# stepper_driver.net
KiCad netlist of a schematic drawn in Altium Designer
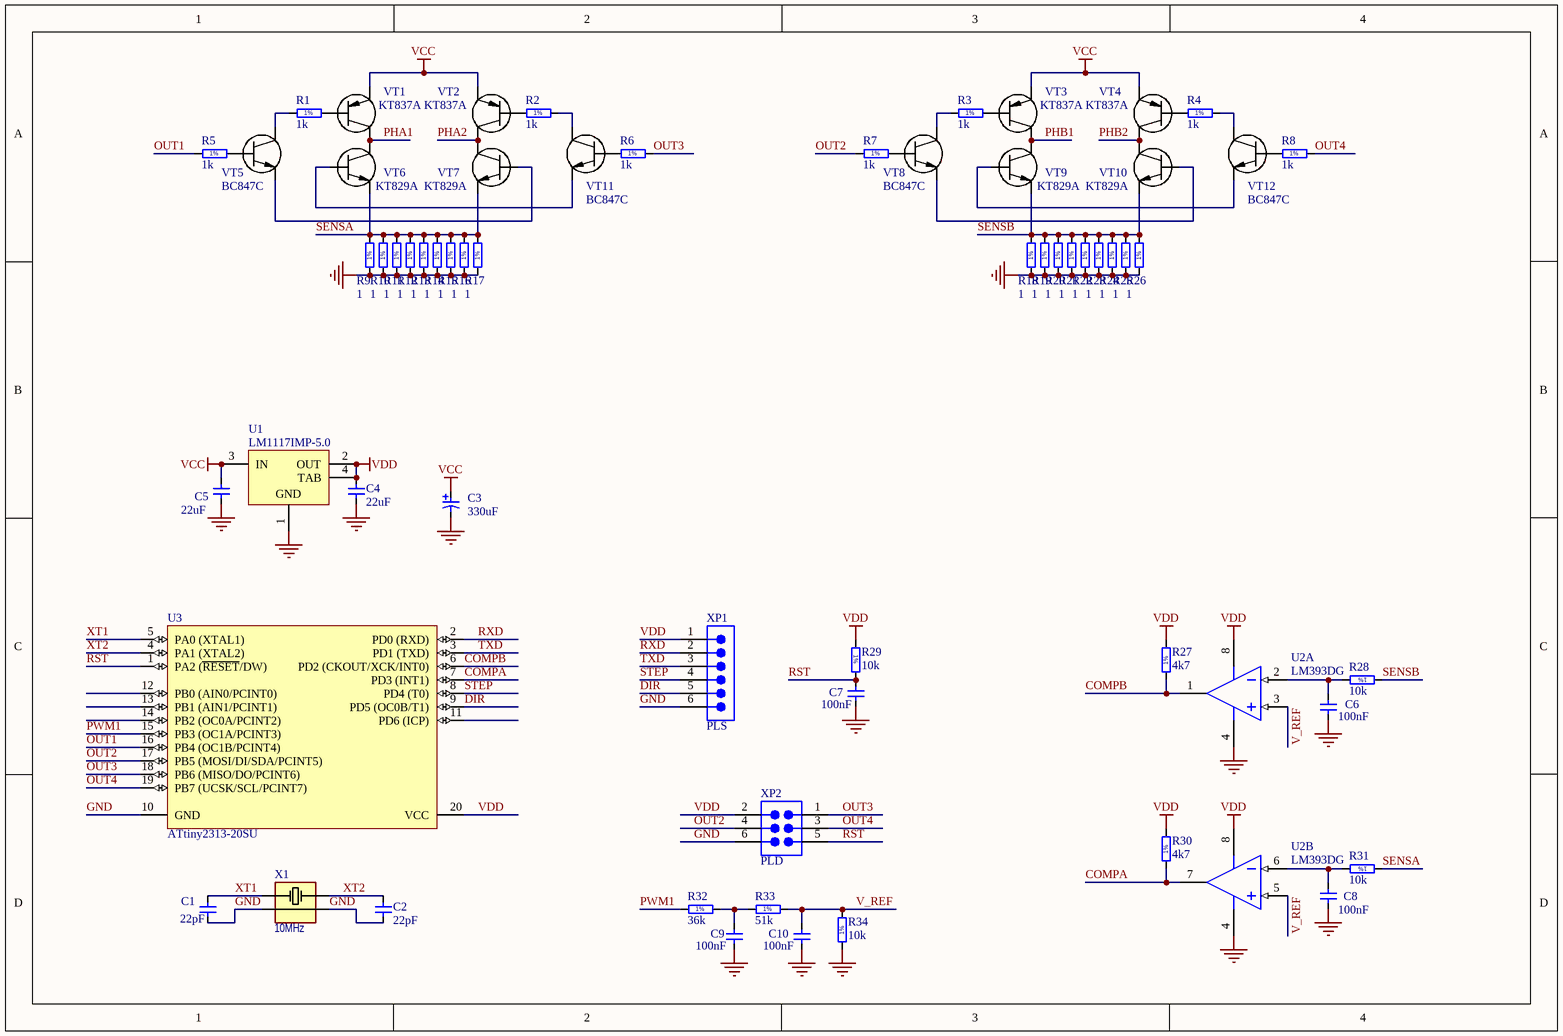
[diagram p0: stepper_driver.SchDoc]

(export (version "E")
  (design (tool "Eeschema 10.0.6"))
  (components
    (comp (ref "C1")
      (value "22pF")
      (footprint "CAP0805R")
      (description "SMD 0805 Capacitor")
      (fields
        (field (name "PART NUMBER") "CC0805_22PF_50V_5%_NP0")
        (field (name "VOLTAGE") "50V")
        (field (name "AUTHOR") "I. Kuznetsov")
      )
      (libsource (lib "Capacitor") (part "CAP_NON_POLAR"))
    )
    (comp (ref "C2")
      (value "22pF")
      (footprint "CAP0805R")
      (description "SMD 0805 Capacitor")
      (fields
        (field (name "PART NUMBER") "CC0805_22PF_50V_5%_NP0")
        (field (name "VOLTAGE") "50V")
        (field (name "AUTHOR") "I. Kuznetsov")
      )
      (libsource (lib "Capacitor") (part "CAP_NON_POLAR"))
    )
    (comp (ref "C3")
      (value "330uF")
      (footprint "TAN_D")
      (fields (field (name "PART NUMBER") "T495D337M010AHE100") (field (name "VOLTAGE") "10V"))
      (libsource (lib "Capacitor") (part "CAP_POLAR"))
    )
    (comp (ref "C4")
      (value "22uF")
      (footprint "CAP0805R")
      (description "SMD 0805 Capacitor")
      (fields
        (field (name "PART NUMBER") "CC0805_22UF_16V_10%_X5R")
        (field (name "VOLTAGE") "16V")
        (field (name "AUTHOR") "I. Kuznetsov")
      )
      (libsource (lib "Capacitor") (part "CAP_NON_POLAR"))
    )
    (comp (ref "C5")
      (value "22uF")
      (footprint "CAP0805R")
      (description "SMD 0805 Capacitor")
      (fields
        (field (name "PART NUMBER") "CC0805_22UF_16V_10%_X5R")
        (field (name "VOLTAGE") "16V")
        (field (name "AUTHOR") "I. Kuznetsov")
      )
      (libsource (lib "Capacitor") (part "CAP_NON_POLAR"))
    )
    (comp (ref "C6")
      (value "100nF")
      (footprint "CAP0805R")
      (description "SMD 0805 Capacitor")
      (fields
        (field (name "PART NUMBER") "CC0805_100NF_50V_10%_X7R")
        (field (name "VOLTAGE") "50V")
        (field (name "AUTHOR") "I. Kuznetsov")
      )
      (libsource (lib "Capacitor") (part "CAP_NON_POLAR"))
    )
    (comp (ref "C7")
      (value "100nF")
      (footprint "CAP0805R")
      (description "SMD 0805 Capacitor")
      (fields
        (field (name "PART NUMBER") "CC0805_100NF_50V_10%_X7R")
        (field (name "VOLTAGE") "50V")
        (field (name "AUTHOR") "I. Kuznetsov")
      )
      (libsource (lib "Capacitor") (part "CAP_NON_POLAR"))
    )
    (comp (ref "C8")
      (value "100nF")
      (footprint "CAP0805R")
      (description "SMD 0805 Capacitor")
      (fields
        (field (name "PART NUMBER") "CC0805_100NF_50V_10%_X7R")
        (field (name "VOLTAGE") "50V")
        (field (name "AUTHOR") "I. Kuznetsov")
      )
      (libsource (lib "Capacitor") (part "CAP_NON_POLAR"))
    )
    (comp (ref "C9")
      (value "100nF")
      (footprint "CAP0805R")
      (description "SMD 0805 Capacitor")
      (fields
        (field (name "PART NUMBER") "CC0805_100NF_50V_10%_X7R")
        (field (name "VOLTAGE") "50V")
        (field (name "AUTHOR") "I. Kuznetsov")
      )
      (libsource (lib "Capacitor") (part "CAP_NON_POLAR"))
    )
    (comp (ref "C10")
      (value "100nF")
      (footprint "CAP0805R")
      (description "SMD 0805 Capacitor")
      (fields
        (field (name "PART NUMBER") "CC0805_100NF_50V_10%_X7R")
        (field (name "VOLTAGE") "50V")
        (field (name "AUTHOR") "I. Kuznetsov")
      )
      (libsource (lib "Capacitor") (part "CAP_NON_POLAR"))
    )
    (comp (ref "R1")
      (value "1k")
      (footprint "RES0805R")
      (fields
        (field (name "PART NUMBER") "R0805_1K_1%_0.125W_100PPM")
        (field (name "POWER") "0.125W")
        (field (name "TOLERANCE") "±1%")
        (field (name "AUTHOR") "CERN DEM JLC")
      )
      (libsource (lib "Resistor") (part "Resistor - 1%"))
    )
    (comp (ref "R2")
      (value "1k")
      (footprint "RES0805R")
      (fields
        (field (name "PART NUMBER") "R0805_1K_1%_0.125W_100PPM")
        (field (name "POWER") "0.125W")
        (field (name "TOLERANCE") "±1%")
        (field (name "AUTHOR") "CERN DEM JLC")
      )
      (libsource (lib "Resistor") (part "Resistor - 1%"))
    )
    (comp (ref "R3")
      (value "1k")
      (footprint "RES0805R")
      (fields
        (field (name "PART NUMBER") "R0805_1K_1%_0.125W_100PPM")
        (field (name "POWER") "0.125W")
        (field (name "TOLERANCE") "±1%")
        (field (name "AUTHOR") "CERN DEM JLC")
      )
      (libsource (lib "Resistor") (part "Resistor - 1%"))
    )
    (comp (ref "R4")
      (value "1k")
      (footprint "RES0805R")
      (fields
        (field (name "PART NUMBER") "R0805_1K_1%_0.125W_100PPM")
        (field (name "POWER") "0.125W")
        (field (name "TOLERANCE") "±1%")
        (field (name "AUTHOR") "CERN DEM JLC")
      )
      (libsource (lib "Resistor") (part "Resistor - 1%"))
    )
    (comp (ref "R5")
      (value "1k")
      (footprint "RES0805R")
      (fields
        (field (name "PART NUMBER") "R0805_1K_1%_0.125W_100PPM")
        (field (name "POWER") "0.125W")
        (field (name "TOLERANCE") "±1%")
        (field (name "AUTHOR") "CERN DEM JLC")
      )
      (libsource (lib "Resistor") (part "Resistor - 1%"))
    )
    (comp (ref "R6")
      (value "1k")
      (footprint "RES0805R")
      (fields
        (field (name "PART NUMBER") "R0805_1K_1%_0.125W_100PPM")
        (field (name "POWER") "0.125W")
        (field (name "TOLERANCE") "±1%")
        (field (name "AUTHOR") "CERN DEM JLC")
      )
      (libsource (lib "Resistor") (part "Resistor - 1%"))
    )
    (comp (ref "R7")
      (value "1k")
      (footprint "RES0805R")
      (fields
        (field (name "PART NUMBER") "R0805_1K_1%_0.125W_100PPM")
        (field (name "POWER") "0.125W")
        (field (name "TOLERANCE") "±1%")
        (field (name "AUTHOR") "CERN DEM JLC")
      )
      (libsource (lib "Resistor") (part "Resistor - 1%"))
    )
    (comp (ref "R8")
      (value "1k")
      (footprint "RES0805R")
      (fields
        (field (name "PART NUMBER") "R0805_1K_1%_0.125W_100PPM")
        (field (name "POWER") "0.125W")
        (field (name "TOLERANCE") "±1%")
        (field (name "AUTHOR") "CERN DEM JLC")
      )
      (libsource (lib "Resistor") (part "Resistor - 1%"))
    )
    (comp (ref "R9")
      (value "1")
      (footprint "RES1206R")
      (fields
        (field (name "PART NUMBER") "R1206_1R_1%_0.25W_200PPM")
        (field (name "POWER") "0.25W")
        (field (name "TOLERANCE") "±1%")
        (field (name "AUTHOR") "CERN DEM JLC")
      )
      (libsource (lib "Resistor") (part "Resistor - 1%"))
    )
    (comp (ref "R10")
      (value "1")
      (footprint "RES1206R")
      (fields
        (field (name "PART NUMBER") "R1206_1R_1%_0.25W_200PPM")
        (field (name "POWER") "0.25W")
        (field (name "TOLERANCE") "±1%")
        (field (name "AUTHOR") "CERN DEM JLC")
      )
      (libsource (lib "Resistor") (part "Resistor - 1%"))
    )
    (comp (ref "R11")
      (value "1")
      (footprint "RES1206R")
      (fields
        (field (name "PART NUMBER") "R1206_1R_1%_0.25W_200PPM")
        (field (name "POWER") "0.25W")
        (field (name "TOLERANCE") "±1%")
        (field (name "AUTHOR") "CERN DEM JLC")
      )
      (libsource (lib "Resistor") (part "Resistor - 1%"))
    )
    (comp (ref "R12")
      (value "1")
      (footprint "RES1206R")
      (fields
        (field (name "PART NUMBER") "R1206_1R_1%_0.25W_200PPM")
        (field (name "POWER") "0.25W")
        (field (name "TOLERANCE") "±1%")
        (field (name "AUTHOR") "CERN DEM JLC")
      )
      (libsource (lib "Resistor") (part "Resistor - 1%"))
    )
    (comp (ref "R13")
      (value "1")
      (footprint "RES1206R")
      (fields
        (field (name "PART NUMBER") "R1206_1R_1%_0.25W_200PPM")
        (field (name "POWER") "0.25W")
        (field (name "TOLERANCE") "±1%")
        (field (name "AUTHOR") "CERN DEM JLC")
      )
      (libsource (lib "Resistor") (part "Resistor - 1%"))
    )
    (comp (ref "R14")
      (value "1")
      (footprint "RES1206R")
      (fields
        (field (name "PART NUMBER") "R1206_1R_1%_0.25W_200PPM")
        (field (name "POWER") "0.25W")
        (field (name "TOLERANCE") "±1%")
        (field (name "AUTHOR") "CERN DEM JLC")
      )
      (libsource (lib "Resistor") (part "Resistor - 1%"))
    )
    (comp (ref "R15")
      (value "1")
      (footprint "RES1206R")
      (fields
        (field (name "PART NUMBER") "R1206_1R_1%_0.25W_200PPM")
        (field (name "POWER") "0.25W")
        (field (name "TOLERANCE") "±1%")
        (field (name "AUTHOR") "CERN DEM JLC")
      )
      (libsource (lib "Resistor") (part "Resistor - 1%"))
    )
    (comp (ref "R16")
      (value "1")
      (footprint "RES1206R")
      (fields
        (field (name "PART NUMBER") "R1206_1R_1%_0.25W_200PPM")
        (field (name "POWER") "0.25W")
        (field (name "TOLERANCE") "±1%")
        (field (name "AUTHOR") "CERN DEM JLC")
      )
      (libsource (lib "Resistor") (part "Resistor - 1%"))
    )
    (comp (ref "R17")
      (value "1")
      (footprint "RES1206R")
      (fields
        (field (name "PART NUMBER") "R1206_1R_1%_0.25W_200PPM")
        (field (name "POWER") "0.25W")
        (field (name "TOLERANCE") "±1%")
        (field (name "AUTHOR") "CERN DEM JLC")
      )
      (libsource (lib "Resistor") (part "Resistor - 1%"))
    )
    (comp (ref "R18")
      (value "1")
      (footprint "RES1206R")
      (fields
        (field (name "PART NUMBER") "R1206_1R_1%_0.25W_200PPM")
        (field (name "POWER") "0.25W")
        (field (name "TOLERANCE") "±1%")
        (field (name "AUTHOR") "CERN DEM JLC")
      )
      (libsource (lib "Resistor") (part "Resistor - 1%"))
    )
    (comp (ref "R19")
      (value "1")
      (footprint "RES1206R")
      (fields
        (field (name "PART NUMBER") "R1206_1R_1%_0.25W_200PPM")
        (field (name "POWER") "0.25W")
        (field (name "TOLERANCE") "±1%")
        (field (name "AUTHOR") "CERN DEM JLC")
      )
      (libsource (lib "Resistor") (part "Resistor - 1%"))
    )
    (comp (ref "R20")
      (value "1")
      (footprint "RES1206R")
      (fields
        (field (name "PART NUMBER") "R1206_1R_1%_0.25W_200PPM")
        (field (name "POWER") "0.25W")
        (field (name "TOLERANCE") "±1%")
        (field (name "AUTHOR") "CERN DEM JLC")
      )
      (libsource (lib "Resistor") (part "Resistor - 1%"))
    )
    (comp (ref "R21")
      (value "1")
      (footprint "RES1206R")
      (fields
        (field (name "PART NUMBER") "R1206_1R_1%_0.25W_200PPM")
        (field (name "POWER") "0.25W")
        (field (name "TOLERANCE") "±1%")
        (field (name "AUTHOR") "CERN DEM JLC")
      )
      (libsource (lib "Resistor") (part "Resistor - 1%"))
    )
    (comp (ref "R22")
      (value "1")
      (footprint "RES1206R")
      (fields
        (field (name "PART NUMBER") "R1206_1R_1%_0.25W_200PPM")
        (field (name "POWER") "0.25W")
        (field (name "TOLERANCE") "±1%")
        (field (name "AUTHOR") "CERN DEM JLC")
      )
      (libsource (lib "Resistor") (part "Resistor - 1%"))
    )
    (comp (ref "R23")
      (value "1")
      (footprint "RES1206R")
      (fields
        (field (name "PART NUMBER") "R1206_1R_1%_0.25W_200PPM")
        (field (name "POWER") "0.25W")
        (field (name "TOLERANCE") "±1%")
        (field (name "AUTHOR") "CERN DEM JLC")
      )
      (libsource (lib "Resistor") (part "Resistor - 1%"))
    )
    (comp (ref "R24")
      (value "1")
      (footprint "RES1206R")
      (fields
        (field (name "PART NUMBER") "R1206_1R_1%_0.25W_200PPM")
        (field (name "POWER") "0.25W")
        (field (name "TOLERANCE") "±1%")
        (field (name "AUTHOR") "CERN DEM JLC")
      )
      (libsource (lib "Resistor") (part "Resistor - 1%"))
    )
    (comp (ref "R25")
      (value "1")
      (footprint "RES1206R")
      (fields
        (field (name "PART NUMBER") "R1206_1R_1%_0.25W_200PPM")
        (field (name "POWER") "0.25W")
        (field (name "TOLERANCE") "±1%")
        (field (name "AUTHOR") "CERN DEM JLC")
      )
      (libsource (lib "Resistor") (part "Resistor - 1%"))
    )
    (comp (ref "R26")
      (value "1")
      (footprint "RES1206R")
      (fields
        (field (name "PART NUMBER") "R1206_1R_1%_0.25W_200PPM")
        (field (name "POWER") "0.25W")
        (field (name "TOLERANCE") "±1%")
        (field (name "AUTHOR") "CERN DEM JLC")
      )
      (libsource (lib "Resistor") (part "Resistor - 1%"))
    )
    (comp (ref "R27")
      (value "4k7")
      (footprint "RES0805R")
      (fields
        (field (name "PART NUMBER") "R0805_4K7_1%_0.125W_100PPM")
        (field (name "POWER") "0.125W")
        (field (name "TOLERANCE") "±1%")
        (field (name "AUTHOR") "CERN DEM JLC")
      )
      (libsource (lib "Resistor") (part "Resistor - 1%"))
    )
    (comp (ref "R28")
      (value "10k")
      (footprint "RES0805R")
      (fields
        (field (name "PART NUMBER") "R0805_10K_1%_0.125W_100PPM")
        (field (name "POWER") "0.125W")
        (field (name "TOLERANCE") "±1%")
        (field (name "AUTHOR") "CERN DEM JLC")
      )
      (libsource (lib "Resistor") (part "Resistor - 1%"))
    )
    (comp (ref "R29")
      (value "10k")
      (footprint "RES0805R")
      (fields
        (field (name "PART NUMBER") "R0805_10K_1%_0.125W_100PPM")
        (field (name "POWER") "0.125W")
        (field (name "TOLERANCE") "±1%")
        (field (name "AUTHOR") "CERN DEM JLC")
      )
      (libsource (lib "Resistor") (part "Resistor - 1%"))
    )
    (comp (ref "R30")
      (value "4k7")
      (footprint "RES0805R")
      (fields
        (field (name "PART NUMBER") "R0805_4K7_1%_0.125W_100PPM")
        (field (name "POWER") "0.125W")
        (field (name "TOLERANCE") "±1%")
        (field (name "AUTHOR") "CERN DEM JLC")
      )
      (libsource (lib "Resistor") (part "Resistor - 1%"))
    )
    (comp (ref "R31")
      (value "10k")
      (footprint "RES0805R")
      (fields
        (field (name "PART NUMBER") "R0805_10K_1%_0.125W_100PPM")
        (field (name "POWER") "0.125W")
        (field (name "TOLERANCE") "±1%")
        (field (name "AUTHOR") "CERN DEM JLC")
      )
      (libsource (lib "Resistor") (part "Resistor - 1%"))
    )
    (comp (ref "R32")
      (value "36k")
      (footprint "RES0805R")
      (fields
        (field (name "PART NUMBER") "R0805_36K_1%_0.125W_100PPM")
        (field (name "POWER") "0.125W")
        (field (name "TOLERANCE") "±1%")
        (field (name "AUTHOR") "CERN DEM JLC")
      )
      (libsource (lib "Resistor") (part "Resistor - 1%"))
    )
    (comp (ref "R33")
      (value "51k")
      (footprint "RES0805R")
      (fields
        (field (name "PART NUMBER") "R0805_51K_1%_0.125W_100PPM")
        (field (name "POWER") "0.125W")
        (field (name "TOLERANCE") "±1%")
        (field (name "AUTHOR") "CERN DEM JLC")
      )
      (libsource (lib "Resistor") (part "Resistor - 1%"))
    )
    (comp (ref "R34")
      (value "10k")
      (footprint "RES0805R")
      (fields
        (field (name "PART NUMBER") "R0805_10K_1%_0.125W_100PPM")
        (field (name "POWER") "0.125W")
        (field (name "TOLERANCE") "±1%")
        (field (name "AUTHOR") "CERN DEM JLC")
      )
      (libsource (lib "Resistor") (part "Resistor - 1%"))
    )
    (comp (ref "U1")
      (value "LM1117IMP-5.0")
      (footprint "MP04A_N")
      (description "800mA Low-Dropout Linear Regulator, 4-pin SOT-223")
      (fields (field (name "MANUFACTURER") "National Semiconductor"))
      (libsource (lib "Altium Content Vault") (part "PM-REG-LM1086-SOT4"))
    )
    (comp (ref "U2")
      (value "LM393DG")
      (footprint "ONSC-SOIC-8-751-07_V")
      (description "Low Offset Voltage Dual Comparators, 2 to 36 V, 0 to 70 degC, 8-Pin SOIC, Pb-Free, Tube")
      (fields (field (name "MANUFACTURER") "On Semiconductor"))
      (libsource (lib "Altium Content Vault") (part "CMP-1305-00047-1"))
    )
    (comp (ref "U3")
      (value "ATtiny2313-20SU")
      (footprint "20S_L")
      (libsource (lib "Altium Content Vault") (part "MC-8B-ATT2313-IL20"))
    )
    (comp (ref "VT1")
      (value "KT837A")
      (footprint "D2PAK")
      (libsource (lib "IC And Semiconductor") (part "PNP_BIPOLAR_D2PAK_INVERSE"))
    )
    (comp (ref "VT2")
      (value "KT837A")
      (footprint "D2PAK")
      (libsource (lib "IC And Semiconductor") (part "PNP_BIPOLAR_D2PAK_INVERSE"))
    )
    (comp (ref "VT3")
      (value "KT837A")
      (footprint "D2PAK")
      (libsource (lib "IC And Semiconductor") (part "PNP_BIPOLAR_D2PAK_INVERSE"))
    )
    (comp (ref "VT4")
      (value "KT837A")
      (footprint "D2PAK")
      (libsource (lib "IC And Semiconductor") (part "PNP_BIPOLAR_D2PAK_INVERSE"))
    )
    (comp (ref "VT5")
      (value "BC847C")
      (footprint "SOT23")
      (fields (field (name "AUTHOR") "I. Kuznetsov"))
      (libsource (lib "IC And Semiconductor") (part "NPN_BIPOLAR_SOT23"))
    )
    (comp (ref "VT6")
      (value "KT829A")
      (footprint "D2PAK")
      (libsource (lib "IC And Semiconductor") (part "NPN_BIPOLAR_D2PAK"))
    )
    (comp (ref "VT7")
      (value "KT829A")
      (footprint "D2PAK")
      (libsource (lib "IC And Semiconductor") (part "NPN_BIPOLAR_D2PAK"))
    )
    (comp (ref "VT8")
      (value "BC847C")
      (footprint "SOT23")
      (fields (field (name "AUTHOR") "I. Kuznetsov"))
      (libsource (lib "IC And Semiconductor") (part "NPN_BIPOLAR_SOT23"))
    )
    (comp (ref "VT9")
      (value "KT829A")
      (footprint "D2PAK")
      (libsource (lib "IC And Semiconductor") (part "NPN_BIPOLAR_D2PAK"))
    )
    (comp (ref "VT10")
      (value "KT829A")
      (footprint "D2PAK")
      (libsource (lib "IC And Semiconductor") (part "NPN_BIPOLAR_D2PAK"))
    )
    (comp (ref "VT11")
      (value "BC847C")
      (footprint "SOT23")
      (fields (field (name "AUTHOR") "I. Kuznetsov"))
      (libsource (lib "IC And Semiconductor") (part "NPN_BIPOLAR_SOT23"))
    )
    (comp (ref "VT12")
      (value "BC847C")
      (footprint "SOT23")
      (fields (field (name "AUTHOR") "I. Kuznetsov"))
      (libsource (lib "IC And Semiconductor") (part "NPN_BIPOLAR_SOT23"))
    )
    (comp (ref "X1")
      (value "10MHz")
      (footprint "5032")
      (description "3*2.5 mm SMD Crystall")
      (fields (field (name "PART NUMBER") "KX-9AT 10.0 MHz 30/50/50 16 pF"))
      (libsource (lib "Crystall") (part "4_PIN_XTAL"))
    )
    (comp (ref "XP1")
      (value "PLS")
      (footprint "PLS-06")
      (fields (field (name "PART NUMBER") "PLS-06") (field (name "MANUFACTURER") "AUK"))
      (libsource (lib "Connector") (part "CN_06P_1W"))
    )
    (comp (ref "XP2")
      (value "PLD")
      (footprint "PLD-06")
      (fields (field (name "PART NUMBER") "PLD-06"))
      (libsource (lib "Connector") (part "CN_06P_2W"))
    )
  )
  (nets
    (net (code "1") (name "/COMPA") (class "Default")
      (node (ref "R30") (pin "1") (pinfunction "1_1") (pintype "passive"))
      (node (ref "U2") (pin "7") (pinfunction "OUTB_7") (pintype "open_collector"))
      (node (ref "U3") (pin "7") (pinfunction "PD3_(INT1)_7") (pintype "bidirectional"))
    )
    (net (code "2") (name "/COMPB") (class "Default")
      (node (ref "R27") (pin "1") (pinfunction "1_1") (pintype "passive"))
      (node (ref "U2") (pin "1") (pinfunction "OUTA_1") (pintype "open_collector"))
      (node (ref "U3") (pin "6") (pinfunction "PD2_(CKOUT/XCK/INT0)_6") (pintype "bidirectional"))
    )
    (net (code "3") (name "/DIR") (class "Default")
      (node (ref "U3") (pin "9") (pinfunction "PD5_(OC0B/T1)_9") (pintype "bidirectional"))
      (node (ref "XP1") (pin "5") (pinfunction "5_5") (pintype "passive"))
    )
    (net (code "4") (name "/OUT1") (class "Default")
      (node (ref "R5") (pin "1") (pinfunction "1_1") (pintype "passive"))
      (node (ref "U3") (pin "16") (pinfunction "PB4_(OC1B/PCINT4)_16") (pintype "bidirectional"))
    )
    (net (code "5") (name "/OUT2") (class "Default")
      (node (ref "R7") (pin "1") (pinfunction "1_1") (pintype "passive"))
      (node (ref "U3") (pin "17") (pinfunction "PB5_(MOSI/DI/SDA/PCINT5)_17") (pintype "bidirectional"))
      (node (ref "XP2") (pin "4") (pinfunction "4_4") (pintype "passive"))
    )
    (net (code "6") (name "/OUT3") (class "Default")
      (node (ref "R6") (pin "2") (pinfunction "2_2") (pintype "passive"))
      (node (ref "U3") (pin "18") (pinfunction "PB6_(MISO/DO/PCINT6)_18") (pintype "bidirectional"))
      (node (ref "XP2") (pin "1") (pinfunction "1_1") (pintype "passive"))
    )
    (net (code "7") (name "/OUT4") (class "Default")
      (node (ref "R8") (pin "2") (pinfunction "2_2") (pintype "passive"))
      (node (ref "U3") (pin "19") (pinfunction "PB7_(UCSK/SCL/PCINT7)_19") (pintype "bidirectional"))
      (node (ref "XP2") (pin "3") (pinfunction "3_3") (pintype "passive"))
    )
    (net (code "8") (name "/PHA1") (class "Default")
      (node (ref "VT1") (pin "3") (pinfunction "C_3") (pintype "passive"))
      (node (ref "VT6") (pin "3") (pinfunction "C_3") (pintype "passive"))
    )
    (net (code "9") (name "/PHA2") (class "Default")
      (node (ref "VT2") (pin "3") (pinfunction "C_3") (pintype "passive"))
      (node (ref "VT7") (pin "3") (pinfunction "C_3") (pintype "passive"))
    )
    (net (code "10") (name "/PHB1") (class "Default")
      (node (ref "VT3") (pin "3") (pinfunction "C_3") (pintype "passive"))
      (node (ref "VT9") (pin "3") (pinfunction "C_3") (pintype "passive"))
    )
    (net (code "11") (name "/PHB2") (class "Default")
      (node (ref "VT10") (pin "3") (pinfunction "C_3") (pintype "passive"))
      (node (ref "VT4") (pin "3") (pinfunction "C_3") (pintype "passive"))
    )
    (net (code "12") (name "/PWM1") (class "Default")
      (node (ref "R32") (pin "1") (pinfunction "1_1") (pintype "passive"))
      (node (ref "U3") (pin "15") (pinfunction "PB3_(OC1A/PCINT3)_15") (pintype "bidirectional"))
    )
    (net (code "13") (name "/RST") (class "Default")
      (node (ref "C7") (pin "2") (pinfunction "2_2") (pintype "passive"))
      (node (ref "R29") (pin "2") (pinfunction "2_2") (pintype "passive"))
      (node (ref "U3") (pin "1") (pinfunction "PA2_(~{RESET}/DW)_1") (pintype "bidirectional"))
      (node (ref "XP2") (pin "5") (pinfunction "5_5") (pintype "passive"))
    )
    (net (code "14") (name "/RXD") (class "Default")
      (node (ref "U3") (pin "2") (pinfunction "PD0_(RXD)_2") (pintype "bidirectional"))
      (node (ref "XP1") (pin "2") (pinfunction "2_2") (pintype "passive"))
    )
    (net (code "15") (name "/SENSA") (class "Default")
      (node (ref "R10") (pin "2") (pinfunction "2_2") (pintype "passive"))
      (node (ref "R11") (pin "2") (pinfunction "2_2") (pintype "passive"))
      (node (ref "R12") (pin "2") (pinfunction "2_2") (pintype "passive"))
      (node (ref "R13") (pin "2") (pinfunction "2_2") (pintype "passive"))
      (node (ref "R14") (pin "2") (pinfunction "2_2") (pintype "passive"))
      (node (ref "R15") (pin "2") (pinfunction "2_2") (pintype "passive"))
      (node (ref "R16") (pin "2") (pinfunction "2_2") (pintype "passive"))
      (node (ref "R17") (pin "2") (pinfunction "2_2") (pintype "passive"))
      (node (ref "R31") (pin "1") (pinfunction "1_1") (pintype "passive"))
      (node (ref "R9") (pin "2") (pinfunction "2_2") (pintype "passive"))
      (node (ref "VT6") (pin "2") (pinfunction "E_2") (pintype "passive"))
      (node (ref "VT7") (pin "2") (pinfunction "E_2") (pintype "passive"))
    )
    (net (code "16") (name "/SENSB") (class "Default")
      (node (ref "R18") (pin "2") (pinfunction "2_2") (pintype "passive"))
      (node (ref "R19") (pin "2") (pinfunction "2_2") (pintype "passive"))
      (node (ref "R20") (pin "2") (pinfunction "2_2") (pintype "passive"))
      (node (ref "R21") (pin "2") (pinfunction "2_2") (pintype "passive"))
      (node (ref "R22") (pin "2") (pinfunction "2_2") (pintype "passive"))
      (node (ref "R23") (pin "2") (pinfunction "2_2") (pintype "passive"))
      (node (ref "R24") (pin "2") (pinfunction "2_2") (pintype "passive"))
      (node (ref "R25") (pin "2") (pinfunction "2_2") (pintype "passive"))
      (node (ref "R26") (pin "2") (pinfunction "2_2") (pintype "passive"))
      (node (ref "R28") (pin "1") (pinfunction "1_1") (pintype "passive"))
      (node (ref "VT10") (pin "2") (pinfunction "E_2") (pintype "passive"))
      (node (ref "VT9") (pin "2") (pinfunction "E_2") (pintype "passive"))
    )
    (net (code "17") (name "/STEP") (class "Default")
      (node (ref "U3") (pin "8") (pinfunction "PD4_(T0)_8") (pintype "bidirectional"))
      (node (ref "XP1") (pin "4") (pinfunction "4_4") (pintype "passive"))
    )
    (net (code "18") (name "/TXD") (class "Default")
      (node (ref "U3") (pin "3") (pinfunction "PD1_(TXD)_3") (pintype "bidirectional"))
      (node (ref "XP1") (pin "3") (pinfunction "3_3") (pintype "passive"))
    )
    (net (code "19") (name "/V_REF") (class "Default")
      (node (ref "C10") (pin "2") (pinfunction "2_2") (pintype "passive"))
      (node (ref "R33") (pin "2") (pinfunction "2_2") (pintype "passive"))
      (node (ref "R34") (pin "2") (pinfunction "2_2") (pintype "passive"))
      (node (ref "U2") (pin "3") (pinfunction "INA+_3") (pintype "input"))
      (node (ref "U2") (pin "5") (pinfunction "INB+_5") (pintype "input"))
    )
    (net (code "20") (name "/XT1") (class "Default")
      (node (ref "C1") (pin "2") (pinfunction "2_2") (pintype "passive"))
      (node (ref "U3") (pin "5") (pinfunction "PA0_(XTAL1)_5") (pintype "bidirectional"))
      (node (ref "X1") (pin "1") (pinfunction "1_1") (pintype "passive"))
    )
    (net (code "21") (name "/XT2") (class "Default")
      (node (ref "C2") (pin "2") (pinfunction "2_2") (pintype "passive"))
      (node (ref "U3") (pin "4") (pinfunction "PA1_(XTAL2)_4") (pintype "bidirectional"))
      (node (ref "X1") (pin "3") (pinfunction "3_3") (pintype "passive"))
    )
    (net (code "22") (name "GND") (class "Default")
      (node (ref "C1") (pin "1") (pinfunction "1_1") (pintype "passive"))
      (node (ref "C10") (pin "1") (pinfunction "1_1") (pintype "passive"))
      (node (ref "C2") (pin "1") (pinfunction "1_1") (pintype "passive"))
      (node (ref "C3") (pin "2") (pinfunction "2_2") (pintype "passive"))
      (node (ref "C4") (pin "1") (pinfunction "1_1") (pintype "passive"))
      (node (ref "C5") (pin "1") (pinfunction "1_1") (pintype "passive"))
      (node (ref "C6") (pin "1") (pinfunction "1_1") (pintype "passive"))
      (node (ref "C7") (pin "1") (pinfunction "1_1") (pintype "passive"))
      (node (ref "C8") (pin "1") (pinfunction "1_1") (pintype "passive"))
      (node (ref "C9") (pin "1") (pinfunction "1_1") (pintype "passive"))
      (node (ref "R10") (pin "1") (pinfunction "1_1") (pintype "passive"))
      (node (ref "R11") (pin "1") (pinfunction "1_1") (pintype "passive"))
      (node (ref "R12") (pin "1") (pinfunction "1_1") (pintype "passive"))
      (node (ref "R13") (pin "1") (pinfunction "1_1") (pintype "passive"))
      (node (ref "R14") (pin "1") (pinfunction "1_1") (pintype "passive"))
      (node (ref "R15") (pin "1") (pinfunction "1_1") (pintype "passive"))
      (node (ref "R16") (pin "1") (pinfunction "1_1") (pintype "passive"))
      (node (ref "R17") (pin "1") (pinfunction "1_1") (pintype "passive"))
      (node (ref "R18") (pin "1") (pinfunction "1_1") (pintype "passive"))
      (node (ref "R19") (pin "1") (pinfunction "1_1") (pintype "passive"))
      (node (ref "R20") (pin "1") (pinfunction "1_1") (pintype "passive"))
      (node (ref "R21") (pin "1") (pinfunction "1_1") (pintype "passive"))
      (node (ref "R22") (pin "1") (pinfunction "1_1") (pintype "passive"))
      (node (ref "R23") (pin "1") (pinfunction "1_1") (pintype "passive"))
      (node (ref "R24") (pin "1") (pinfunction "1_1") (pintype "passive"))
      (node (ref "R25") (pin "1") (pinfunction "1_1") (pintype "passive"))
      (node (ref "R26") (pin "1") (pinfunction "1_1") (pintype "passive"))
      (node (ref "R34") (pin "1") (pinfunction "1_1") (pintype "passive"))
      (node (ref "R9") (pin "1") (pinfunction "1_1") (pintype "passive"))
      (node (ref "U1") (pin "1") (pinfunction "GND_1") (pintype "power_in"))
      (node (ref "U2") (pin "4") (pinfunction "GND_4") (pintype "power_in"))
      (node (ref "U3") (pin "10") (pinfunction "GND_10") (pintype "power_in"))
      (node (ref "X1") (pin "2") (pinfunction "2_2") (pintype "passive"))
      (node (ref "X1") (pin "4") (pinfunction "4_4") (pintype "passive"))
      (node (ref "XP1") (pin "6") (pinfunction "6_6") (pintype "passive"))
      (node (ref "XP2") (pin "6") (pinfunction "6_6") (pintype "passive"))
    )
    (net (code "23") (name "Net-(C9-Pad2)") (class "Default")
      (node (ref "C9") (pin "2") (pinfunction "2_2") (pintype "passive"))
      (node (ref "R32") (pin "2") (pinfunction "2_2") (pintype "passive"))
      (node (ref "R33") (pin "1") (pinfunction "1_1") (pintype "passive"))
    )
    (net (code "24") (name "Net-(U2A-INA-)") (class "Default")
      (node (ref "C6") (pin "2") (pinfunction "2_2") (pintype "passive"))
      (node (ref "R28") (pin "2") (pinfunction "2_2") (pintype "passive"))
      (node (ref "U2") (pin "2") (pinfunction "INA-_2") (pintype "input"))
    )
    (net (code "25") (name "Net-(U2B-INB-)") (class "Default")
      (node (ref "C8") (pin "2") (pinfunction "2_2") (pintype "passive"))
      (node (ref "R31") (pin "2") (pinfunction "2_2") (pintype "passive"))
      (node (ref "U2") (pin "6") (pinfunction "INB-_6") (pintype "input"))
    )
    (net (code "26") (name "Net-(VT1-B)") (class "Default")
      (node (ref "R1") (pin "2") (pinfunction "2_2") (pintype "passive"))
      (node (ref "VT1") (pin "2") (pinfunction "B_2") (pintype "passive"))
    )
    (net (code "27") (name "Net-(VT2-B)") (class "Default")
      (node (ref "R2") (pin "1") (pinfunction "1_1") (pintype "passive"))
      (node (ref "VT2") (pin "2") (pinfunction "B_2") (pintype "passive"))
    )
    (net (code "28") (name "Net-(VT3-B)") (class "Default")
      (node (ref "R3") (pin "2") (pinfunction "2_2") (pintype "passive"))
      (node (ref "VT3") (pin "2") (pinfunction "B_2") (pintype "passive"))
    )
    (net (code "29") (name "Net-(VT4-B)") (class "Default")
      (node (ref "R4") (pin "1") (pinfunction "1_1") (pintype "passive"))
      (node (ref "VT4") (pin "2") (pinfunction "B_2") (pintype "passive"))
    )
    (net (code "30") (name "Net-(VT5-B)") (class "Default")
      (node (ref "R5") (pin "2") (pinfunction "2_2") (pintype "passive"))
      (node (ref "VT5") (pin "1") (pinfunction "B_1") (pintype "passive"))
    )
    (net (code "31") (name "Net-(VT5-C)") (class "Default")
      (node (ref "R1") (pin "1") (pinfunction "1_1") (pintype "passive"))
      (node (ref "VT5") (pin "3") (pinfunction "C_3") (pintype "passive"))
    )
    (net (code "32") (name "Net-(VT5-E)") (class "Default")
      (node (ref "VT5") (pin "2") (pinfunction "E_2") (pintype "passive"))
      (node (ref "VT7") (pin "1") (pinfunction "B_1") (pintype "passive"))
    )
    (net (code "33") (name "Net-(VT8-B)") (class "Default")
      (node (ref "R7") (pin "2") (pinfunction "2_2") (pintype "passive"))
      (node (ref "VT8") (pin "1") (pinfunction "B_1") (pintype "passive"))
    )
    (net (code "34") (name "Net-(VT8-C)") (class "Default")
      (node (ref "R3") (pin "1") (pinfunction "1_1") (pintype "passive"))
      (node (ref "VT8") (pin "3") (pinfunction "C_3") (pintype "passive"))
    )
    (net (code "35") (name "Net-(VT10-B)") (class "Default")
      (node (ref "VT10") (pin "1") (pinfunction "B_1") (pintype "passive"))
      (node (ref "VT8") (pin "2") (pinfunction "E_2") (pintype "passive"))
    )
    (net (code "36") (name "Net-(VT11-B)") (class "Default")
      (node (ref "R6") (pin "1") (pinfunction "1_1") (pintype "passive"))
      (node (ref "VT11") (pin "1") (pinfunction "B_1") (pintype "passive"))
    )
    (net (code "37") (name "Net-(VT11-C)") (class "Default")
      (node (ref "R2") (pin "2") (pinfunction "2_2") (pintype "passive"))
      (node (ref "VT11") (pin "3") (pinfunction "C_3") (pintype "passive"))
    )
    (net (code "38") (name "Net-(VT11-E)") (class "Default")
      (node (ref "VT11") (pin "2") (pinfunction "E_2") (pintype "passive"))
      (node (ref "VT6") (pin "1") (pinfunction "B_1") (pintype "passive"))
    )
    (net (code "39") (name "Net-(VT12-B)") (class "Default")
      (node (ref "R8") (pin "1") (pinfunction "1_1") (pintype "passive"))
      (node (ref "VT12") (pin "1") (pinfunction "B_1") (pintype "passive"))
    )
    (net (code "40") (name "Net-(VT12-C)") (class "Default")
      (node (ref "R4") (pin "2") (pinfunction "2_2") (pintype "passive"))
      (node (ref "VT12") (pin "3") (pinfunction "C_3") (pintype "passive"))
    )
    (net (code "41") (name "Net-(VT12-E)") (class "Default")
      (node (ref "VT12") (pin "2") (pinfunction "E_2") (pintype "passive"))
      (node (ref "VT9") (pin "1") (pinfunction "B_1") (pintype "passive"))
    )
    (net (code "42") (name "VCC") (class "Default")
      (node (ref "C3") (pin "1") (pinfunction "1_1") (pintype "passive"))
      (node (ref "C5") (pin "2") (pinfunction "2_2") (pintype "passive"))
      (node (ref "U1") (pin "3") (pinfunction "IN_3") (pintype "power_in"))
      (node (ref "VT1") (pin "1") (pinfunction "E_1") (pintype "passive"))
      (node (ref "VT2") (pin "1") (pinfunction "E_1") (pintype "passive"))
      (node (ref "VT3") (pin "1") (pinfunction "E_1") (pintype "passive"))
      (node (ref "VT4") (pin "1") (pinfunction "E_1") (pintype "passive"))
    )
    (net (code "43") (name "VDD") (class "Default")
      (node (ref "C4") (pin "2") (pinfunction "2_2") (pintype "passive"))
      (node (ref "R27") (pin "2") (pinfunction "2_2") (pintype "passive"))
      (node (ref "R29") (pin "1") (pinfunction "1_1") (pintype "passive"))
      (node (ref "R30") (pin "2") (pinfunction "2_2") (pintype "passive"))
      (node (ref "U1") (pin "2") (pinfunction "OUT_2") (pintype "power_in"))
      (node (ref "U1") (pin "4") (pinfunction "TAB_4") (pintype "power_in"))
      (node (ref "U2") (pin "8") (pinfunction "VCC_8") (pintype "power_in"))
      (node (ref "U3") (pin "20") (pinfunction "VCC_20") (pintype "power_in"))
      (node (ref "XP1") (pin "1") (pinfunction "1_1") (pintype "passive"))
      (node (ref "XP2") (pin "2") (pinfunction "2_2") (pintype "passive"))
    )
    (net (code "44") (name "unconnected-(U3-PB0_(AIN0{slash}PCINT0)-Pad12)") (class "Default")
      (node (ref "U3") (pin "12") (pinfunction "PB0_(AIN0/PCINT0)_12") (pintype "bidirectional"))
    )
    (net (code "45") (name "unconnected-(U3-PB1_(AIN1{slash}PCINT1)-Pad13)") (class "Default")
      (node (ref "U3") (pin "13") (pinfunction "PB1_(AIN1/PCINT1)_13") (pintype "bidirectional"))
    )
    (net (code "46") (name "unconnected-(U3-PB2_(OC0A{slash}PCINT2)-Pad14)") (class "Default")
      (node (ref "U3") (pin "14") (pinfunction "PB2_(OC0A/PCINT2)_14") (pintype "bidirectional"))
    )
    (net (code "47") (name "unconnected-(U3-PD6_(ICP)-Pad11)") (class "Default")
      (node (ref "U3") (pin "11") (pinfunction "PD6_(ICP)_11") (pintype "bidirectional"))
    )
  )
)
